# SK-Additional_keys.net
KiCad netlist of a schematic drawn in Altium Designer
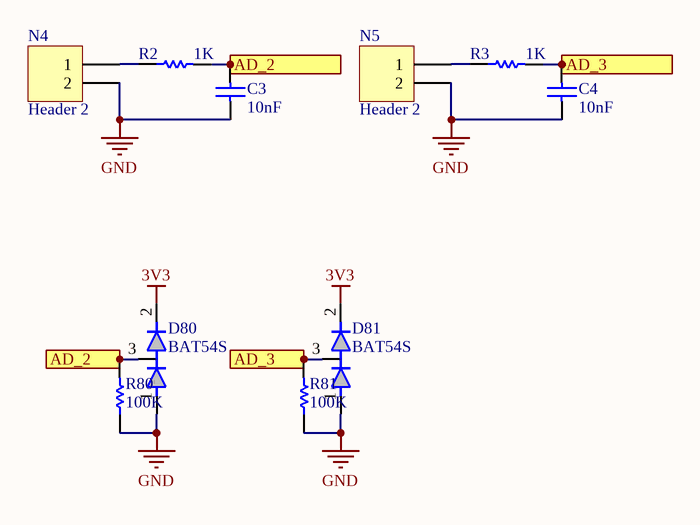
[diagram p0: SK-Additional_keys.SchDoc]

(export (version "E")
  (design (tool "Eeschema 10.0.6"))
  (components
    (comp (ref "C3")
      (value "10nF")
      (footprint "SMH_RES0805-STD")
      (description "Capacitor")
      (fields (field (name "PUBLISHER") "Altium Limited"))
      (libsource (lib "Miscellaneous Devices") (part "Cap"))
    )
    (comp (ref "C4")
      (value "10nF")
      (footprint "SMH_RES0805-STD")
      (description "Capacitor")
      (fields (field (name "PUBLISHER") "Altium Limited"))
      (libsource (lib "Miscellaneous Devices") (part "Cap"))
    )
    (comp (ref "D80") (value "BAT54S") (footprint "SMH_SOT-23") (libsource (lib "Mlib") (part "BAT54S")))
    (comp (ref "D81") (value "BAT54S") (footprint "SMH_SOT-23") (libsource (lib "Mlib") (part "BAT54S")))
    (comp (ref "N4")
      (value "Header 2")
      (footprint "SMH_HDR1X2")
      (description "Header, 2-Pin")
      (fields (field (name "PUBLISHER") "Altium Limited"))
      (libsource (lib "Miscellaneous Connectors") (part "Header 2"))
    )
    (comp (ref "N5")
      (value "Header 2")
      (footprint "SMH_HDR1X2")
      (description "Header, 2-Pin")
      (fields (field (name "PUBLISHER") "Altium Limited"))
      (libsource (lib "Miscellaneous Connectors") (part "Header 2"))
    )
    (comp (ref "R2")
      (value "1K")
      (footprint "SMH_RES0805-STD")
      (description "Resistor")
      (fields (field (name "PUBLISHER") "Altium Limited"))
      (libsource (lib "Miscellaneous Devices") (part "Res1"))
    )
    (comp (ref "R3")
      (value "1K")
      (footprint "SMH_RES0805-STD")
      (description "Resistor")
      (fields (field (name "PUBLISHER") "Altium Limited"))
      (libsource (lib "Miscellaneous Devices") (part "Res1"))
    )
    (comp (ref "R80")
      (value "100K")
      (footprint "SMH_RES0805-STD")
      (description "Resistor")
      (fields (field (name "PUBLISHER") "Altium Limited"))
      (libsource (lib "Miscellaneous Devices") (part "Res1"))
    )
    (comp (ref "R81")
      (value "100K")
      (footprint "SMH_RES0805-STD")
      (description "Resistor")
      (fields (field (name "PUBLISHER") "Altium Limited"))
      (libsource (lib "Miscellaneous Devices") (part "Res1"))
    )
  )
  (nets
    (net (code "1") (name "/AD_2") (class "Default")
      (node (ref "C3") (pin "1") (pinfunction "1_1") (pintype "passive"))
      (node (ref "D80") (pin "3") (pinfunction "3_3") (pintype "passive"))
      (node (ref "R2") (pin "2") (pinfunction "2_2") (pintype "passive"))
      (node (ref "R80") (pin "2") (pinfunction "2_2") (pintype "passive"))
    )
    (net (code "2") (name "/AD_3") (class "Default")
      (node (ref "C4") (pin "1") (pinfunction "1_1") (pintype "passive"))
      (node (ref "D81") (pin "3") (pinfunction "3_3") (pintype "passive"))
      (node (ref "R3") (pin "2") (pinfunction "2_2") (pintype "passive"))
      (node (ref "R81") (pin "2") (pinfunction "2_2") (pintype "passive"))
    )
    (net (code "3") (name "3V3") (class "Default")
      (node (ref "D80") (pin "2") (pinfunction "2_2") (pintype "passive"))
      (node (ref "D81") (pin "2") (pinfunction "2_2") (pintype "passive"))
    )
    (net (code "4") (name "GND") (class "Default")
      (node (ref "C3") (pin "2") (pinfunction "2_2") (pintype "passive"))
      (node (ref "C4") (pin "2") (pinfunction "2_2") (pintype "passive"))
      (node (ref "D80") (pin "1") (pinfunction "1_1") (pintype "passive"))
      (node (ref "D81") (pin "1") (pinfunction "1_1") (pintype "passive"))
      (node (ref "N4") (pin "2") (pinfunction "2_2") (pintype "passive"))
      (node (ref "N5") (pin "2") (pinfunction "2_2") (pintype "passive"))
      (node (ref "R80") (pin "1") (pinfunction "1_1") (pintype "passive"))
      (node (ref "R81") (pin "1") (pinfunction "1_1") (pintype "passive"))
    )
    (net (code "5") (name "Net-(N4-Pad1)") (class "Default")
      (node (ref "N4") (pin "1") (pinfunction "1_1") (pintype "passive"))
      (node (ref "R2") (pin "1") (pinfunction "1_1") (pintype "passive"))
    )
    (net (code "6") (name "Net-(N5-Pad1)") (class "Default")
      (node (ref "N5") (pin "1") (pinfunction "1_1") (pintype "passive"))
      (node (ref "R3") (pin "1") (pinfunction "1_1") (pintype "passive"))
    )
  )
)
